# Connectivity.net
KiCad netlist of a schematic drawn in Altium Designer
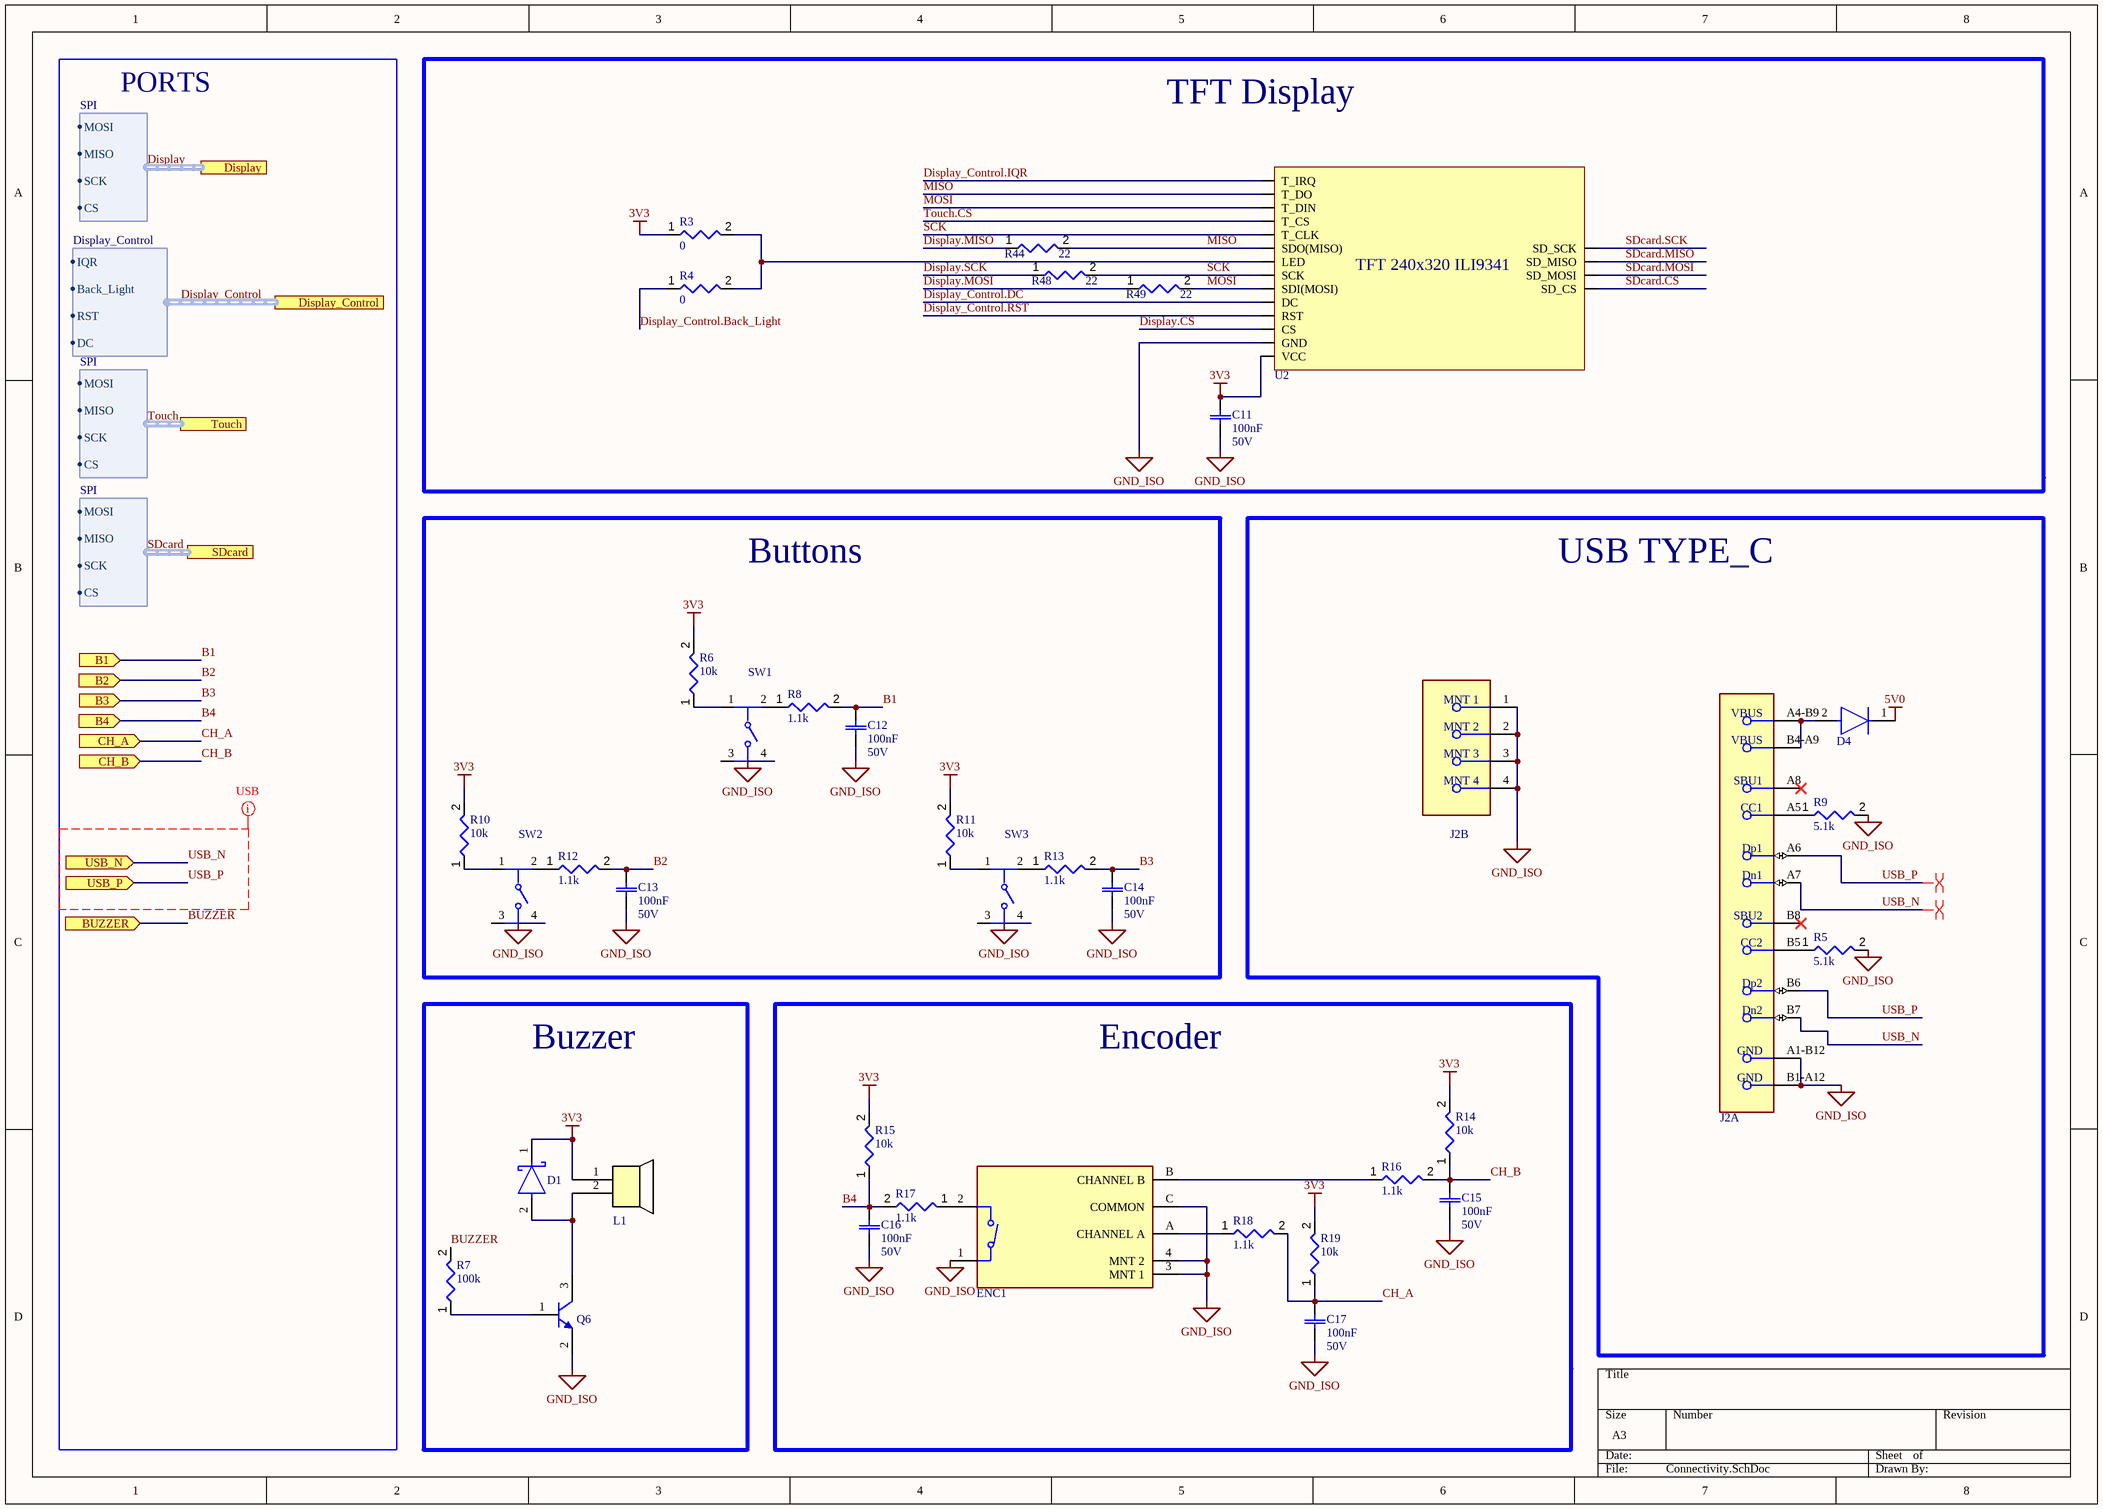
[diagram p0: Connectivity.SchDoc]

(export (version "E")
  (design (tool "Eeschema 10.0.6"))
  (components
    (comp (ref "C11")
      (value "100nF")
      (footprint "Generic Ceramic 0603 CAP")
      (fields
        (field (name "VOLTAGE RATING") "50V")
        (field (name "Comment") "CAP-MLCC_SMD-0603_MR-GCM_u_0.1uF_50V_10%_X8L")
      )
      (libsource (lib "Paulo Peixoto") (part "CAP_Ceramic"))
    )
    (comp (ref "C12")
      (value "100nF")
      (footprint "Generic Ceramic 0603 CAP")
      (fields
        (field (name "VOLTAGE RATING") "50V")
        (field (name "Comment") "CAP-MLCC_SMD-0603_MR-GCM_u_0.1uF_50V_10%_X8L")
      )
      (libsource (lib "Paulo Peixoto") (part "CAP_Ceramic"))
    )
    (comp (ref "C13")
      (value "100nF")
      (footprint "Generic Ceramic 0603 CAP")
      (fields
        (field (name "VOLTAGE RATING") "50V")
        (field (name "Comment") "CAP-MLCC_SMD-0603_MR-GCM_u_0.1uF_50V_10%_X8L")
      )
      (libsource (lib "Paulo Peixoto") (part "CAP_Ceramic"))
    )
    (comp (ref "C14")
      (value "100nF")
      (footprint "Generic Ceramic 0603 CAP")
      (fields
        (field (name "VOLTAGE RATING") "50V")
        (field (name "Comment") "CAP-MLCC_SMD-0603_MR-GCM_u_0.1uF_50V_10%_X8L")
      )
      (libsource (lib "Paulo Peixoto") (part "CAP_Ceramic"))
    )
    (comp (ref "C15")
      (value "100nF")
      (footprint "Generic Ceramic 0603 CAP")
      (fields
        (field (name "VOLTAGE RATING") "50V")
        (field (name "Comment") "CAP-MLCC_SMD-0603_MR-GCM_u_0.1uF_50V_10%_X8L")
      )
      (libsource (lib "Paulo Peixoto") (part "CAP_Ceramic"))
    )
    (comp (ref "C16")
      (value "100nF")
      (footprint "Generic Ceramic 0603 CAP")
      (fields
        (field (name "VOLTAGE RATING") "50V")
        (field (name "Comment") "CAP-MLCC_SMD-0603_MR-GCM_u_0.1uF_50V_10%_X8L")
      )
      (libsource (lib "Paulo Peixoto") (part "CAP_Ceramic"))
    )
    (comp (ref "C17")
      (value "100nF")
      (footprint "Generic Ceramic 0603 CAP")
      (fields
        (field (name "VOLTAGE RATING") "50V")
        (field (name "Comment") "CAP-MLCC_SMD-0603_MR-GCM_u_0.1uF_50V_10%_X8L")
      )
      (libsource (lib "Paulo Peixoto") (part "CAP_Ceramic"))
    )
    (comp (ref "D1")
      (value "DIO-SHOTTKY_SMD_OD-214AC_TWS-1A_100V")
      (footprint "DIO-SHOTTKY_SMD_OD-214AC_TWS-1A_100V-Footprint-1")
      (description "Rectifier Diode, Schottky, 1 Phase, 1 Element, 1A, 100V V(RRM), Silicon, DO-214AC")
      (fields (field (name "MANUFACTURER PART NUMBER") "SS110"))
      (libsource (lib "Paulo Peixoto") (part "Generic_Shottky_Diode"))
    )
    (comp (ref "D4")
      (value "RS1A")
      (footprint "FP-403AE-MFG")
      (description "Diode Fast Recovery Rectifier 50V 1A 2-Pin DO-214AC T/R")
      (libsource (lib "Paulo Peixoto") (part "d7152d700b627762746794eb795d46e"))
    )
    (comp (ref "ENC1")
      (value "PEC11R-4020F-S0012")
      (footprint "FP-PEC11R-4020F-S0012-MFG")
      (description "ROTARY ENCODER MECHANICAL 12PPR")
      (libsource (lib "Altium Content Vault") (part "e87796756a4d1ac046a6b3c733736c6"))
    )
    (comp (ref "J2")
      (value "217179-0001")
      (footprint "FP-2171790001-MFG")
      (description "CONN RCP USB2.0 TYP C 24P SMD RA")
      (libsource (lib "Altium Content Vault") (part "8b86497a633d14b3f74642136fc0ce6"))
    )
    (comp (ref "L1")
      (value "TMB12A05")
      (footprint "TMB12A05-Footprint-1")
      (description "88dB Active (Built-in Driver Circuit) Electromagnetic Type 2.4kHz Plugin, D=12mm Buzzers ROHS")
      (libsource (lib "Paulo Peixoto") (part "TMB12A05-Symbol-1"))
    )
    (comp (ref "Q6")
      (value "SMMBT2222ALT1G")
      (footprint "ONSC-SOT-23-3-318-08_V")
      (description "General Purpose Transistor, NPN Silicon, 3-Pin SOT-23, Pb-Free, Tape and Reel")
      (fields (field (name "MANUFACTURER") "On Semiconductor"))
      (libsource (lib "Altium Content Vault") (part "ONSC-NPN-B1E2C3-3"))
    )
    (comp (ref "R3")
      (value "0")
      (footprint "Generic_0603_RES")
      (description "Resistor SMD 0 Ohm 0603 PU=5000 ST, CRCW06030000Z0EA, Vishay")
      (fields (field (name "TOLERANCE") "1%") (field (name "POWER") "100mW"))
      (libsource (lib "Paulo Peixoto") (part "Res"))
    )
    (comp (ref "R4")
      (value "0")
      (footprint "Generic_0603_RES")
      (description "Resistor SMD 0 Ohm 0603 PU=5000 ST, CRCW06030000Z0EA, Vishay")
      (fields (field (name "TOLERANCE") "1%") (field (name "POWER") "100mW"))
      (libsource (lib "Paulo Peixoto") (part "Res"))
    )
    (comp (ref "R5")
      (value "5.1k")
      (footprint "Generic_0603_RES")
      (fields
        (field (name "POWER") "100mW")
        (field (name "TOLERANCE") "1%")
        (field (name "Comment") "RES-TK_SMD-0603_VIS-CRCW_K_5.1K_1/10W_1%")
      )
      (libsource (lib "Paulo Peixoto") (part "Res"))
    )
    (comp (ref "R6")
      (value "10k")
      (footprint "Generic_0603_RES")
      (fields
        (field (name "TOLERANCE") "1%")
        (field (name "POWER") "100mW")
        (field (name "Comment") "RES-TK_SMD-0603_VIS-CRCW_K_10K_1/10W_1%")
      )
      (libsource (lib "Paulo Peixoto") (part "Res"))
    )
    (comp (ref "R7")
      (value "100k")
      (footprint "Generic_0603_RES")
      (fields
        (field (name "POWER") "100mW")
        (field (name "TOLERANCE") "1%")
        (field (name "Comment") "RES-TK_SMD-0603_VIS-CRCW_K_100K_1/10W_1%")
      )
      (libsource (lib "Paulo Peixoto") (part "Res"))
    )
    (comp (ref "R8")
      (value "1.1k")
      (footprint "Generic_0603_RES")
      (fields
        (field (name "POWER") "100mW")
        (field (name "TOLERANCE") "1%")
        (field (name "Comment") "RES-TK_SMD-0603_VIS-CRCW_K_1.1K_1/10W_1%")
      )
      (libsource (lib "Paulo Peixoto") (part "Res"))
    )
    (comp (ref "R9")
      (value "5.1k")
      (footprint "Generic_0603_RES")
      (fields
        (field (name "POWER") "100mW")
        (field (name "TOLERANCE") "1%")
        (field (name "Comment") "RES-TK_SMD-0603_VIS-CRCW_K_5.1K_1/10W_1%")
      )
      (libsource (lib "Paulo Peixoto") (part "Res"))
    )
    (comp (ref "R10")
      (value "10k")
      (footprint "Generic_0603_RES")
      (fields
        (field (name "TOLERANCE") "1%")
        (field (name "POWER") "100mW")
        (field (name "Comment") "RES-TK_SMD-0603_VIS-CRCW_K_10K_1/10W_1%")
      )
      (libsource (lib "Paulo Peixoto") (part "Res"))
    )
    (comp (ref "R11")
      (value "10k")
      (footprint "Generic_0603_RES")
      (fields
        (field (name "TOLERANCE") "1%")
        (field (name "POWER") "100mW")
        (field (name "Comment") "RES-TK_SMD-0603_VIS-CRCW_K_10K_1/10W_1%")
      )
      (libsource (lib "Paulo Peixoto") (part "Res"))
    )
    (comp (ref "R12")
      (value "1.1k")
      (footprint "Generic_0603_RES")
      (fields
        (field (name "POWER") "100mW")
        (field (name "TOLERANCE") "1%")
        (field (name "Comment") "RES-TK_SMD-0603_VIS-CRCW_K_1.1K_1/10W_1%")
      )
      (libsource (lib "Paulo Peixoto") (part "Res"))
    )
    (comp (ref "R13")
      (value "1.1k")
      (footprint "Generic_0603_RES")
      (fields
        (field (name "POWER") "100mW")
        (field (name "TOLERANCE") "1%")
        (field (name "Comment") "RES-TK_SMD-0603_VIS-CRCW_K_1.1K_1/10W_1%")
      )
      (libsource (lib "Paulo Peixoto") (part "Res"))
    )
    (comp (ref "R14")
      (value "10k")
      (footprint "Generic_0603_RES")
      (fields
        (field (name "TOLERANCE") "1%")
        (field (name "POWER") "100mW")
        (field (name "Comment") "RES-TK_SMD-0603_VIS-CRCW_K_10K_1/10W_1%")
      )
      (libsource (lib "Paulo Peixoto") (part "Res"))
    )
    (comp (ref "R15")
      (value "10k")
      (footprint "Generic_0603_RES")
      (fields
        (field (name "TOLERANCE") "1%")
        (field (name "POWER") "100mW")
        (field (name "Comment") "RES-TK_SMD-0603_VIS-CRCW_K_10K_1/10W_1%")
      )
      (libsource (lib "Paulo Peixoto") (part "Res"))
    )
    (comp (ref "R16")
      (value "1.1k")
      (footprint "Generic_0603_RES")
      (fields
        (field (name "POWER") "100mW")
        (field (name "TOLERANCE") "1%")
        (field (name "Comment") "RES-TK_SMD-0603_VIS-CRCW_K_1.1K_1/10W_1%")
      )
      (libsource (lib "Paulo Peixoto") (part "Res"))
    )
    (comp (ref "R17")
      (value "1.1k")
      (footprint "Generic_0603_RES")
      (fields
        (field (name "POWER") "100mW")
        (field (name "TOLERANCE") "1%")
        (field (name "Comment") "RES-TK_SMD-0603_VIS-CRCW_K_1.1K_1/10W_1%")
      )
      (libsource (lib "Paulo Peixoto") (part "Res"))
    )
    (comp (ref "R18")
      (value "1.1k")
      (footprint "Generic_0603_RES")
      (fields
        (field (name "POWER") "100mW")
        (field (name "TOLERANCE") "1%")
        (field (name "Comment") "RES-TK_SMD-0603_VIS-CRCW_K_1.1K_1/10W_1%")
      )
      (libsource (lib "Paulo Peixoto") (part "Res"))
    )
    (comp (ref "R19")
      (value "10k")
      (footprint "Generic_0603_RES")
      (fields
        (field (name "TOLERANCE") "1%")
        (field (name "POWER") "100mW")
        (field (name "Comment") "RES-TK_SMD-0603_VIS-CRCW_K_10K_1/10W_1%")
      )
      (libsource (lib "Paulo Peixoto") (part "Res"))
    )
    (comp (ref "R44")
      (value "22")
      (footprint "Generic_0603_RES")
      (description "Res Thick Film 0603 22 Ohm 1% 1/10W ±100ppm/°C Molded SMD Paper T/R")
      (fields (field (name "POWER") "125mW") (field (name "TOLERANCE") "1%"))
      (libsource (lib "Paulo Peixoto") (part "Res"))
    )
    (comp (ref "R48")
      (value "22")
      (footprint "Generic_0603_RES")
      (description "Res Thick Film 0603 22 Ohm 1% 1/10W ±100ppm/°C Molded SMD Paper T/R")
      (fields (field (name "POWER") "125mW") (field (name "TOLERANCE") "1%"))
      (libsource (lib "Paulo Peixoto") (part "Res"))
    )
    (comp (ref "R49")
      (value "22")
      (footprint "Generic_0603_RES")
      (description "Res Thick Film 0603 22 Ohm 1% 1/10W ±100ppm/°C Molded SMD Paper T/R")
      (fields (field (name "POWER") "125mW") (field (name "TOLERANCE") "1%"))
      (libsource (lib "Paulo Peixoto") (part "Res"))
    )
    (comp (ref "SW1")
      (value "TL1105AF160Q")
      (footprint "FP-TL1105AF160Q-MFG")
      (description "SWITCH TACTILE SPST-NO 0.05A 12V")
      (libsource (lib "Altium Content Vault") (part "82b636f13fd696edb7519609c0a8a76"))
    )
    (comp (ref "SW2")
      (value "TL1105AF160Q")
      (footprint "FP-TL1105AF160Q-MFG")
      (description "SWITCH TACTILE SPST-NO 0.05A 12V")
      (libsource (lib "Altium Content Vault") (part "82b636f13fd696edb7519609c0a8a76"))
    )
    (comp (ref "SW3")
      (value "TL1105AF160Q")
      (footprint "FP-TL1105AF160Q-MFG")
      (description "SWITCH TACTILE SPST-NO 0.05A 12V")
      (libsource (lib "Altium Content Vault") (part "82b636f13fd696edb7519609c0a8a76"))
    )
    (comp (ref "U2")
      (value "TFT 240x320 SPI")
      (footprint "TFT ILI9341 2.4inch")
      (libsource (lib "Paulo Peixoto") (part "TFT 240x320 SPI -Symbol-1"))
    )
  )
  (nets
    (net (code "5") (name "/B1") (class "Default")
      (node (ref "C12") (pin "2") (pinfunction "2_2") (pintype "passive"))
      (node (ref "R8") (pin "2") (pinfunction "2_2") (pintype "passive"))
    )
    (net (code "6") (name "/B2") (class "Default")
      (node (ref "C13") (pin "2") (pinfunction "2_2") (pintype "passive"))
      (node (ref "R12") (pin "2") (pinfunction "2_2") (pintype "passive"))
    )
    (net (code "7") (name "/B3") (class "Default")
      (node (ref "C14") (pin "2") (pinfunction "2_2") (pintype "passive"))
      (node (ref "R13") (pin "2") (pinfunction "2_2") (pintype "passive"))
    )
    (net (code "8") (name "/B4") (class "Default")
      (node (ref "C16") (pin "2") (pinfunction "2_2") (pintype "passive"))
      (node (ref "R15") (pin "1") (pinfunction "1_1") (pintype "passive"))
      (node (ref "R17") (pin "2") (pinfunction "2_2") (pintype "passive"))
    )
    (net (code "9") (name "/BUZZER") (class "Default")
      (node (ref "R7") (pin "2") (pinfunction "2_2") (pintype "passive"))
    )
    (net (code "10") (name "/CH_A") (class "Default")
      (node (ref "C17") (pin "2") (pinfunction "2_2") (pintype "passive"))
      (node (ref "R18") (pin "2") (pinfunction "2_2") (pintype "passive"))
      (node (ref "R19") (pin "1") (pinfunction "1_1") (pintype "passive"))
    )
    (net (code "11") (name "/CH_B") (class "Default")
      (node (ref "C15") (pin "2") (pinfunction "2_2") (pintype "passive"))
      (node (ref "R14") (pin "1") (pinfunction "1_1") (pintype "passive"))
      (node (ref "R16") (pin "2") (pinfunction "2_2") (pintype "passive"))
    )
    (net (code "12") (name "/Display.CS") (class "Default")
      (node (ref "U2") (pin "3") (pinfunction "CS_3") (pintype "passive"))
    )
    (net (code "13") (name "/Display.MISO") (class "Default")
      (node (ref "R44") (pin "1") (pinfunction "1_1") (pintype "passive"))
    )
    (net (code "14") (name "/Display.MOSI") (class "Default")
      (node (ref "R49") (pin "1") (pinfunction "1_1") (pintype "passive"))
    )
    (net (code "15") (name "/Display.SCK") (class "Default")
      (node (ref "R48") (pin "1") (pinfunction "1_1") (pintype "passive"))
    )
    (net (code "16") (name "/Display_Control.Back_Light") (class "Default")
      (node (ref "R4") (pin "1") (pinfunction "1_1") (pintype "passive"))
    )
    (net (code "17") (name "/Display_Control.DC") (class "Default")
      (node (ref "U2") (pin "5") (pinfunction "DC_5") (pintype "passive"))
    )
    (net (code "18") (name "/Display_Control.IQR") (class "Default")
      (node (ref "U2") (pin "14") (pinfunction "T_IRQ_14") (pintype "passive"))
    )
    (net (code "19") (name "/Display_Control.RST") (class "Default")
      (node (ref "U2") (pin "4") (pinfunction "RST_4") (pintype "passive"))
    )
    (net (code "22") (name "/MISO") (class "Default")
      (node (ref "R44") (pin "2") (pinfunction "2_2") (pintype "passive"))
      (node (ref "U2") (pin "13") (pinfunction "T_DO_13") (pintype "passive"))
      (node (ref "U2") (pin "9") (pinfunction "SDO(MISO)_9") (pintype "passive"))
    )
    (net (code "23") (name "/MOSI") (class "Default")
      (node (ref "R49") (pin "2") (pinfunction "2_2") (pintype "passive"))
      (node (ref "U2") (pin "12") (pinfunction "T_DIN_12") (pintype "passive"))
      (node (ref "U2") (pin "6") (pinfunction "SDI(MOSI)_6") (pintype "passive"))
    )
    (net (code "24") (name "/SCK") (class "Default")
      (node (ref "R48") (pin "2") (pinfunction "2_2") (pintype "passive"))
      (node (ref "U2") (pin "10") (pinfunction "T_CLK_10") (pintype "passive"))
      (node (ref "U2") (pin "7") (pinfunction "SCK_7") (pintype "passive"))
    )
    (net (code "25") (name "/SDcard.CS") (class "Default")
      (node (ref "U2") (pin "18") (pinfunction "SD_CS_18") (pintype "passive"))
    )
    (net (code "26") (name "/SDcard.MISO") (class "Default")
      (node (ref "U2") (pin "16") (pinfunction "SD_MISO_16") (pintype "passive"))
    )
    (net (code "27") (name "/SDcard.MOSI") (class "Default")
      (node (ref "U2") (pin "17") (pinfunction "SD_MOSI_17") (pintype "passive"))
    )
    (net (code "28") (name "/SDcard.SCK") (class "Default")
      (node (ref "U2") (pin "15") (pinfunction "SD_SCK_15") (pintype "passive"))
    )
    (net (code "30") (name "/Touch.CS") (class "Default")
      (node (ref "U2") (pin "11") (pinfunction "T_CS_11") (pintype "passive"))
    )
    (net (code "32") (name "/USB_N") (class "Default")
      (node (ref "J2") (pin "A7") (pinfunction "Dn1_A7") (pintype "bidirectional"))
      (node (ref "J2") (pin "B7") (pinfunction "Dn2_B7") (pintype "bidirectional"))
    )
    (net (code "33") (name "/USB_P") (class "Default")
      (node (ref "J2") (pin "A6") (pinfunction "Dp1_A6") (pintype "bidirectional"))
      (node (ref "J2") (pin "B6") (pinfunction "Dp2_B6") (pintype "bidirectional"))
    )
    (net (code "34") (name "3V3") (class "Default")
      (node (ref "C11") (pin "2") (pinfunction "2_2") (pintype "passive"))
      (node (ref "D1") (pin "1") (pinfunction "C_1") (pintype "passive"))
      (node (ref "L1") (pin "1") (pinfunction "1_1") (pintype "passive"))
      (node (ref "R10") (pin "2") (pinfunction "2_2") (pintype "passive"))
      (node (ref "R11") (pin "2") (pinfunction "2_2") (pintype "passive"))
      (node (ref "R14") (pin "2") (pinfunction "2_2") (pintype "passive"))
      (node (ref "R15") (pin "2") (pinfunction "2_2") (pintype "passive"))
      (node (ref "R19") (pin "2") (pinfunction "2_2") (pintype "passive"))
      (node (ref "R3") (pin "1") (pinfunction "1_1") (pintype "passive"))
      (node (ref "R6") (pin "2") (pinfunction "2_2") (pintype "passive"))
      (node (ref "U2") (pin "1") (pinfunction "VCC_1") (pintype "passive"))
    )
    (net (code "35") (name "5V0") (class "Default")
      (node (ref "D4") (pin "1") (pinfunction "C_1") (pintype "passive"))
    )
    (net (code "36") (name "GND_ISO") (class "Default")
      (node (ref "C11") (pin "1") (pinfunction "1_1") (pintype "passive"))
      (node (ref "C12") (pin "1") (pinfunction "1_1") (pintype "passive"))
      (node (ref "C13") (pin "1") (pinfunction "1_1") (pintype "passive"))
      (node (ref "C14") (pin "1") (pinfunction "1_1") (pintype "passive"))
      (node (ref "C15") (pin "1") (pinfunction "1_1") (pintype "passive"))
      (node (ref "C16") (pin "1") (pinfunction "1_1") (pintype "passive"))
      (node (ref "C17") (pin "1") (pinfunction "1_1") (pintype "passive"))
      (node (ref "ENC1") (pin "1") (pinfunction "1_1") (pintype "passive"))
      (node (ref "ENC1") (pin "3") (pinfunction "MNT_1_3") (pintype "passive"))
      (node (ref "ENC1") (pin "4") (pinfunction "MNT_2_4") (pintype "passive"))
      (node (ref "ENC1") (pin "C") (pinfunction "COMMON_C") (pintype "passive"))
      (node (ref "J2") (pin "1") (pinfunction "MNT_1_1") (pintype "passive"))
      (node (ref "J2") (pin "2") (pinfunction "MNT_2_2") (pintype "passive"))
      (node (ref "J2") (pin "3") (pinfunction "MNT_3_3") (pintype "power_in"))
      (node (ref "J2") (pin "4") (pinfunction "MNT_4_4") (pintype "power_in"))
      (node (ref "J2") (pin "A1-B12") (pinfunction "GND_A1-B12") (pintype "power_in"))
      (node (ref "J2") (pin "B1-A12") (pinfunction "GND_B1-A12") (pintype "power_in"))
      (node (ref "Q6") (pin "2") (pinfunction "E_2") (pintype "passive"))
      (node (ref "R5") (pin "2") (pinfunction "2_2") (pintype "passive"))
      (node (ref "R9") (pin "2") (pinfunction "2_2") (pintype "passive"))
      (node (ref "SW1") (pin "4") (pinfunction "4_4") (pintype "passive"))
      (node (ref "SW2") (pin "4") (pinfunction "4_4") (pintype "passive"))
      (node (ref "SW3") (pin "4") (pinfunction "4_4") (pintype "passive"))
      (node (ref "U2") (pin "2") (pinfunction "GND_2") (pintype "passive"))
    )
    (net (code "37") (name "Net-(D1-A)") (class "Default")
      (node (ref "D1") (pin "2") (pinfunction "A_2") (pintype "passive"))
      (node (ref "L1") (pin "2") (pinfunction "2_2") (pintype "passive"))
      (node (ref "Q6") (pin "3") (pinfunction "C_3") (pintype "passive"))
    )
    (net (code "38") (name "Net-(D4-A)") (class "Default")
      (node (ref "D4") (pin "2") (pinfunction "A_2") (pintype "passive"))
      (node (ref "J2") (pin "A4-B9") (pinfunction "VBUS_A4-B9") (pintype "power_in"))
      (node (ref "J2") (pin "B4-A9") (pinfunction "VBUS_B4-A9") (pintype "power_in"))
    )
    (net (code "39") (name "Net-(ENC1-CHANNEL_A)") (class "Default")
      (node (ref "ENC1") (pin "A") (pinfunction "CHANNEL_A_A") (pintype "passive"))
      (node (ref "R18") (pin "1") (pinfunction "1_1") (pintype "passive"))
    )
    (net (code "40") (name "Net-(ENC1-CHANNEL_B)") (class "Default")
      (node (ref "ENC1") (pin "B") (pinfunction "CHANNEL_B_B") (pintype "passive"))
      (node (ref "R16") (pin "1") (pinfunction "1_1") (pintype "passive"))
    )
    (net (code "41") (name "Net-(ENC1-Pad2)") (class "Default")
      (node (ref "ENC1") (pin "2") (pinfunction "2_2") (pintype "passive"))
      (node (ref "R17") (pin "1") (pinfunction "1_1") (pintype "passive"))
    )
    (net (code "42") (name "Net-(J2A-CC1)") (class "Default")
      (node (ref "J2") (pin "A5") (pinfunction "CC1_A5") (pintype "passive"))
      (node (ref "R9") (pin "1") (pinfunction "1_1") (pintype "passive"))
    )
    (net (code "43") (name "Net-(J2A-CC2)") (class "Default")
      (node (ref "J2") (pin "B5") (pinfunction "CC2_B5") (pintype "passive"))
      (node (ref "R5") (pin "1") (pinfunction "1_1") (pintype "passive"))
    )
    (net (code "44") (name "Net-(Q6-B)") (class "Default")
      (node (ref "Q6") (pin "1") (pinfunction "B_1") (pintype "passive"))
      (node (ref "R7") (pin "1") (pinfunction "1_1") (pintype "passive"))
    )
    (net (code "45") (name "Net-(R6-Pad1)") (class "Default")
      (node (ref "R6") (pin "1") (pinfunction "1_1") (pintype "passive"))
      (node (ref "SW1") (pin "1") (pinfunction "1_1") (pintype "passive"))
    )
    (net (code "46") (name "Net-(R8-Pad1)") (class "Default")
      (node (ref "R8") (pin "1") (pinfunction "1_1") (pintype "passive"))
      (node (ref "SW1") (pin "2") (pinfunction "2_2") (pintype "passive"))
    )
    (net (code "47") (name "Net-(R10-Pad1)") (class "Default")
      (node (ref "R10") (pin "1") (pinfunction "1_1") (pintype "passive"))
      (node (ref "SW2") (pin "1") (pinfunction "1_1") (pintype "passive"))
    )
    (net (code "48") (name "Net-(R11-Pad1)") (class "Default")
      (node (ref "R11") (pin "1") (pinfunction "1_1") (pintype "passive"))
      (node (ref "SW3") (pin "1") (pinfunction "1_1") (pintype "passive"))
    )
    (net (code "49") (name "Net-(R12-Pad1)") (class "Default")
      (node (ref "R12") (pin "1") (pinfunction "1_1") (pintype "passive"))
      (node (ref "SW2") (pin "2") (pinfunction "2_2") (pintype "passive"))
    )
    (net (code "50") (name "Net-(R13-Pad1)") (class "Default")
      (node (ref "R13") (pin "1") (pinfunction "1_1") (pintype "passive"))
      (node (ref "SW3") (pin "2") (pinfunction "2_2") (pintype "passive"))
    )
    (net (code "51") (name "Net-(U2-LED)") (class "Default")
      (node (ref "R3") (pin "2") (pinfunction "2_2") (pintype "passive"))
      (node (ref "R4") (pin "2") (pinfunction "2_2") (pintype "passive"))
      (node (ref "U2") (pin "8") (pinfunction "LED_8") (pintype "passive"))
    )
    (net (code "52") (name "unconnected-(J2A-SBU1-PadA8)") (class "Default")
      (node (ref "J2") (pin "A8") (pinfunction "SBU1_A8") (pintype "passive+no_connect"))
    )
    (net (code "53") (name "unconnected-(J2A-SBU2-PadB8)") (class "Default")
      (node (ref "J2") (pin "B8") (pinfunction "SBU2_B8") (pintype "passive+no_connect"))
    )
    (net (code "54") (name "unconnected-(SW1-Pad3)") (class "Default")
      (node (ref "SW1") (pin "3") (pinfunction "3_3") (pintype "passive"))
    )
    (net (code "55") (name "unconnected-(SW2-Pad3)") (class "Default")
      (node (ref "SW2") (pin "3") (pinfunction "3_3") (pintype "passive"))
    )
    (net (code "56") (name "unconnected-(SW3-Pad3)") (class "Default")
      (node (ref "SW3") (pin "3") (pinfunction "3_3") (pintype "passive"))
    )
  )
)
